# HB-UNI-SenAct-4-4-RC_V2_2.net
KiCad netlist of a schematic drawn in EAGLE
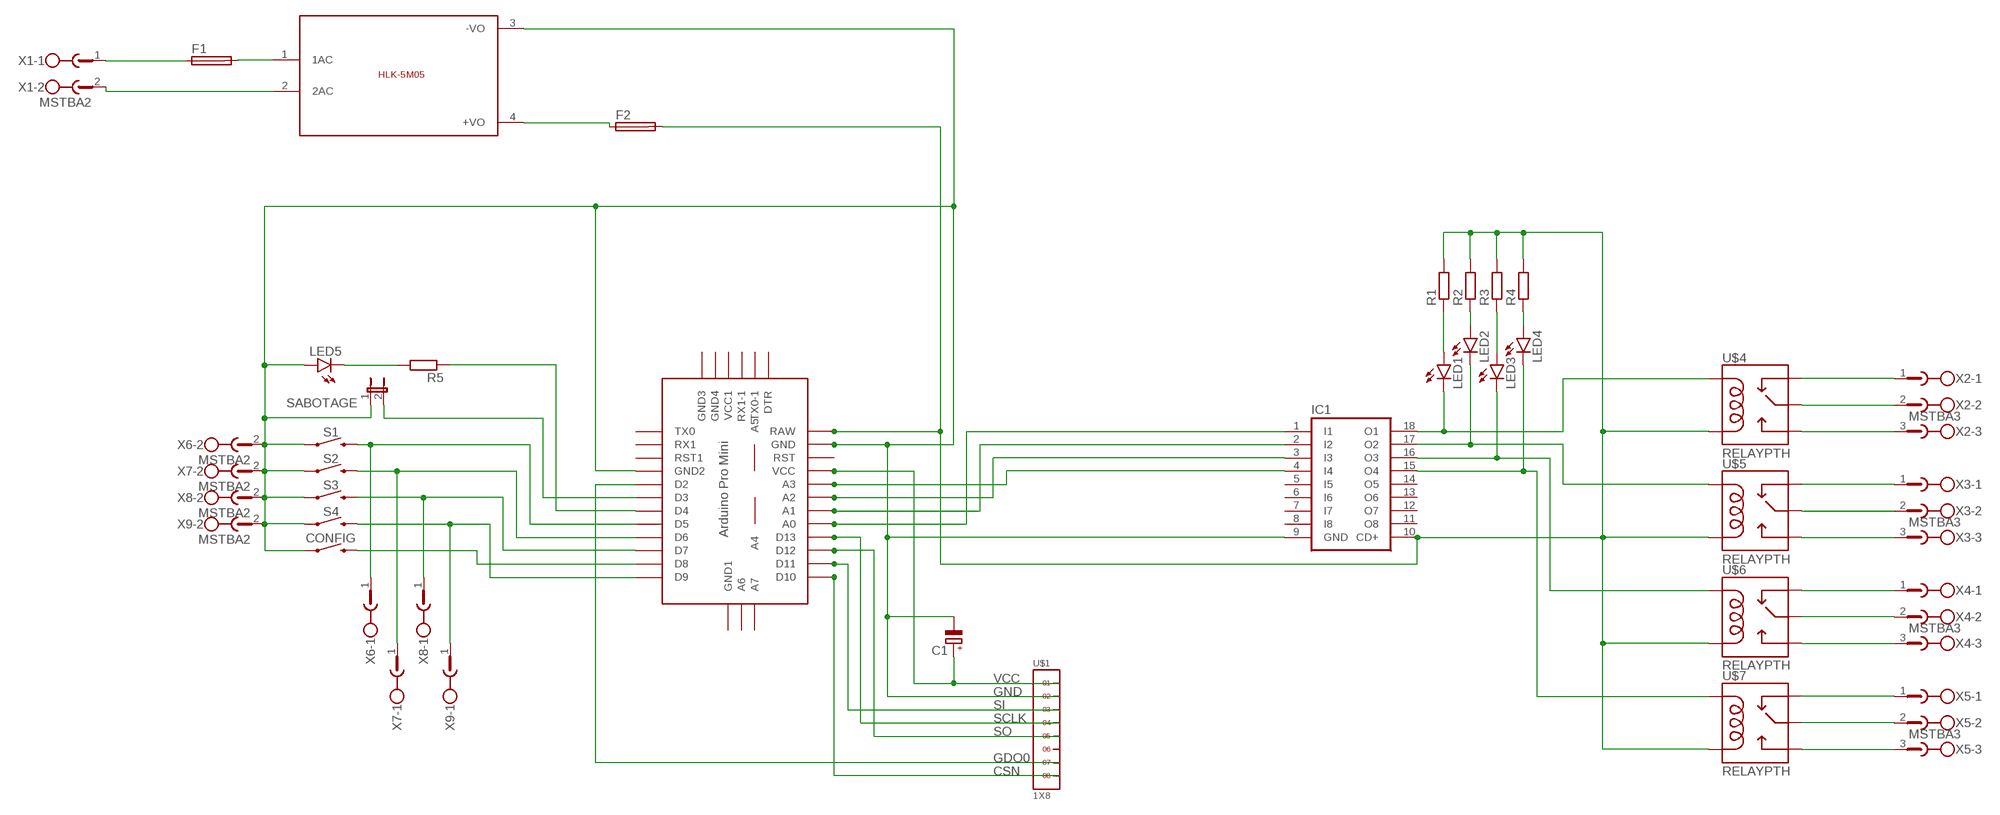
[diagram p0: schematic, sheet 1]

(export (version "E")
  (design (tool "Eeschema 10.0.6"))
  (components
    (comp (ref "C1")
      (value "CPOL-EUE2.5-5")
      (footprint "eagle-import:E2,5-5")
      (libsource (lib "eagle-import") (part "CPOL-EUE2.5-5"))
    )
    (comp (ref "CONFIG")
      (value "MOMENTARY-SWITCH-SPST-PTH-6.0MM-KIT")
      (footprint "eagle-import:TACTILE_SWITCH_PTH_6.0MM_KIT")
      (libsource (lib "eagle-import") (part "MOMENTARY-SWITCH-SPST-PTH-6.0MM-KIT"))
    )
    (comp (ref "F1")
      (value "SH22,5A")
      (footprint "eagle-import:SH22,5A")
      (fields (field (name "MPN") "0031.7701.11"))
      (libsource (lib "eagle-import") (part "SH22,5A"))
    )
    (comp (ref "F2")
      (value "SH22,5A")
      (footprint "eagle-import:SH22,5A")
      (fields (field (name "MPN") "0031.7701.11"))
      (libsource (lib "eagle-import") (part "SH22,5A"))
    )
    (comp (ref "IC1")
      (value "ULN2803A")
      (footprint "eagle-import:DIL18")
      (libsource (lib "eagle-import") (part "ULN2803A"))
    )
    (comp (ref "LED1")
      (value "LED3MM")
      (footprint "eagle-import:LED3MM")
      (libsource (lib "eagle-import") (part "LED3MM"))
    )
    (comp (ref "LED2")
      (value "LED3MM")
      (footprint "eagle-import:LED3MM")
      (libsource (lib "eagle-import") (part "LED3MM"))
    )
    (comp (ref "LED3")
      (value "LED3MM")
      (footprint "eagle-import:LED3MM")
      (libsource (lib "eagle-import") (part "LED3MM"))
    )
    (comp (ref "LED4")
      (value "LED3MM")
      (footprint "eagle-import:LED3MM")
      (libsource (lib "eagle-import") (part "LED3MM"))
    )
    (comp (ref "LED5")
      (value "LED3MM")
      (footprint "eagle-import:LED3MM")
      (libsource (lib "eagle-import") (part "LED3MM"))
    )
    (comp (ref "R1")
      (value "R-EU_0309/10")
      (footprint "eagle-import:0309_10")
      (libsource (lib "eagle-import") (part "R-EU_0309/10"))
    )
    (comp (ref "R2")
      (value "R-EU_0309/10")
      (footprint "eagle-import:0309_10")
      (libsource (lib "eagle-import") (part "R-EU_0309/10"))
    )
    (comp (ref "R3")
      (value "R-EU_0309/10")
      (footprint "eagle-import:0309_10")
      (libsource (lib "eagle-import") (part "R-EU_0309/10"))
    )
    (comp (ref "R4")
      (value "R-EU_0309/10")
      (footprint "eagle-import:0309_10")
      (libsource (lib "eagle-import") (part "R-EU_0309/10"))
    )
    (comp (ref "R5")
      (value "R-EU_0309/10")
      (footprint "eagle-import:0309_10")
      (libsource (lib "eagle-import") (part "R-EU_0309/10"))
    )
    (comp (ref "S1")
      (value "MOMENTARY-SWITCH-SPST-PTH-6.0MM")
      (footprint "eagle-import:TACTILE_SWITCH_PTH_6.0MM")
      (libsource (lib "eagle-import") (part "MOMENTARY-SWITCH-SPST-PTH-6.0MM"))
    )
    (comp (ref "S2")
      (value "MOMENTARY-SWITCH-SPST-PTH-6.0MM-KIT")
      (footprint "eagle-import:TACTILE_SWITCH_PTH_6.0MM_KIT")
      (libsource (lib "eagle-import") (part "MOMENTARY-SWITCH-SPST-PTH-6.0MM-KIT"))
    )
    (comp (ref "S3")
      (value "MOMENTARY-SWITCH-SPST-PTH-6.0MM-KIT")
      (footprint "eagle-import:TACTILE_SWITCH_PTH_6.0MM_KIT")
      (libsource (lib "eagle-import") (part "MOMENTARY-SWITCH-SPST-PTH-6.0MM-KIT"))
    )
    (comp (ref "S4")
      (value "MOMENTARY-SWITCH-SPST-PTH-6.0MM-KIT")
      (footprint "eagle-import:TACTILE_SWITCH_PTH_6.0MM_KIT")
      (libsource (lib "eagle-import") (part "MOMENTARY-SWITCH-SPST-PTH-6.0MM-KIT"))
    )
    (comp (ref "SABOTAGE")
      (value "JP1E")
      (footprint "eagle-import:JP1")
      (libsource (lib "eagle-import") (part "JP1E"))
    )
    (comp (ref "U$1")
      (value "1X8")
      (footprint "eagle-import:1X8")
      (libsource (lib "eagle-import") (part "1X8"))
    )
    (comp (ref "U$2")
      (value "ABK-PRO-MINI")
      (footprint "eagle-import:ABK-PRO-MINI")
      (libsource (lib "eagle-import") (part "ABK-PRO-MINI"))
    )
    (comp (ref "U$3")
      (value "5VDC/5W")
      (footprint "eagle-import:HLK-5M05")
      (libsource (lib "eagle-import") (part "HLK-5M05"))
    )
    (comp (ref "U$4")
      (value "RELAYPTH")
      (footprint "eagle-import:SRD-05VDC-SL-C")
      (libsource (lib "eagle-import") (part "RELAYPTH"))
    )
    (comp (ref "U$5")
      (value "RELAYPTH")
      (footprint "eagle-import:SRD-05VDC-SL-C")
      (libsource (lib "eagle-import") (part "RELAYPTH"))
    )
    (comp (ref "U$6")
      (value "RELAYPTH")
      (footprint "eagle-import:SRD-05VDC-SL-C")
      (libsource (lib "eagle-import") (part "RELAYPTH"))
    )
    (comp (ref "U$7")
      (value "RELAYPTH")
      (footprint "eagle-import:SRD-05VDC-SL-C")
      (libsource (lib "eagle-import") (part "RELAYPTH"))
    )
    (comp (ref "X1")
      (value "MSTBA2")
      (footprint "eagle-import:MSTBA2")
      (fields (field (name "MF") "FARNELL") (field (name "MPN") "1757242"))
      (libsource (lib "eagle-import") (part "MSTBA2"))
    )
    (comp (ref "X2")
      (value "MSTBA3")
      (footprint "eagle-import:MSTBA3")
      (fields (field (name "MF") "FARNELL") (field (name "MPN") "1757255"))
      (libsource (lib "eagle-import") (part "MSTBA3"))
    )
    (comp (ref "X3")
      (value "MSTBA3")
      (footprint "eagle-import:MSTBA3")
      (fields (field (name "MF") "FARNELL") (field (name "MPN") "1757255"))
      (libsource (lib "eagle-import") (part "MSTBA3"))
    )
    (comp (ref "X4")
      (value "MSTBA3")
      (footprint "eagle-import:MSTBA3")
      (fields (field (name "MF") "FARNELL") (field (name "MPN") "1757255"))
      (libsource (lib "eagle-import") (part "MSTBA3"))
    )
    (comp (ref "X5")
      (value "MSTBA3")
      (footprint "eagle-import:MSTBA3")
      (fields (field (name "MF") "FARNELL") (field (name "MPN") "1757255"))
      (libsource (lib "eagle-import") (part "MSTBA3"))
    )
    (comp (ref "X6")
      (value "MSTBA2")
      (footprint "eagle-import:MSTBA2")
      (fields (field (name "MF") "FARNELL") (field (name "MPN") "1757242"))
      (libsource (lib "eagle-import") (part "MSTBA2"))
    )
    (comp (ref "X7")
      (value "MSTBA2")
      (footprint "eagle-import:MSTBA2")
      (fields (field (name "MF") "FARNELL") (field (name "MPN") "1757242"))
      (libsource (lib "eagle-import") (part "MSTBA2"))
    )
    (comp (ref "X8")
      (value "MSTBA2")
      (footprint "eagle-import:MSTBA2")
      (fields (field (name "MF") "FARNELL") (field (name "MPN") "1757242"))
      (libsource (lib "eagle-import") (part "MSTBA2"))
    )
    (comp (ref "X9")
      (value "MSTBA2")
      (footprint "eagle-import:MSTBA2")
      (fields (field (name "MF") "FARNELL") (field (name "MPN") "1757242"))
      (libsource (lib "eagle-import") (part "MSTBA2"))
    )
  )
  (nets
    (net (code "1") (name "/CSN") (class "Default")
      (node (ref "U$1") (pin "8") (pinfunction "8_8") (pintype "bidirectional"))
      (node (ref "U$2") (pin "D10") (pinfunction "D10_D10") (pintype "bidirectional"))
    )
    (net (code "2") (name "/GDO0") (class "Default")
      (node (ref "U$1") (pin "7") (pinfunction "7_7") (pintype "bidirectional"))
      (node (ref "U$2") (pin "D2") (pinfunction "D2_D2") (pintype "bidirectional"))
    )
    (net (code "3") (name "/GND") (class "Default")
      (node (ref "C1") (pin "-") (pinfunction "-_-") (pintype "passive"))
      (node (ref "CONFIG") (pin "1") (pinfunction "1_1") (pintype "passive"))
      (node (ref "IC1") (pin "9") (pinfunction "GND_9") (pintype "power_in"))
      (node (ref "LED5") (pin "A") (pinfunction "A_A") (pintype "passive"))
      (node (ref "S1") (pin "1") (pinfunction "1_1") (pintype "passive"))
      (node (ref "S2") (pin "1") (pinfunction "1_1") (pintype "passive"))
      (node (ref "S3") (pin "1") (pinfunction "1_1") (pintype "passive"))
      (node (ref "S4") (pin "1") (pinfunction "1_1") (pintype "passive"))
      (node (ref "SABOTAGE") (pin "1") (pinfunction "1_1") (pintype "passive"))
      (node (ref "U$1") (pin "2") (pinfunction "2_2") (pintype "bidirectional"))
      (node (ref "U$2") (pin "GND") (pinfunction "GND_GND") (pintype "bidirectional"))
      (node (ref "U$2") (pin "GND1") (pinfunction "GND2_GND1") (pintype "bidirectional"))
      (node (ref "U$3") (pin "3") (pinfunction "-VO_3") (pintype "bidirectional"))
      (node (ref "X6") (pin "2") (pinfunction "1_2") (pintype "passive"))
      (node (ref "X7") (pin "2") (pinfunction "1_2") (pintype "passive"))
      (node (ref "X8") (pin "2") (pinfunction "1_2") (pintype "passive"))
      (node (ref "X9") (pin "2") (pinfunction "1_2") (pintype "passive"))
    )
    (net (code "4") (name "/SCLK") (class "Default")
      (node (ref "U$1") (pin "4") (pinfunction "4_4") (pintype "bidirectional"))
      (node (ref "U$2") (pin "D13") (pinfunction "D13_D13") (pintype "bidirectional"))
    )
    (net (code "5") (name "/SI") (class "Default")
      (node (ref "U$1") (pin "3") (pinfunction "3_3") (pintype "bidirectional"))
      (node (ref "U$2") (pin "D11") (pinfunction "D11_D11") (pintype "bidirectional"))
    )
    (net (code "6") (name "/SO") (class "Default")
      (node (ref "U$1") (pin "5") (pinfunction "5_5") (pintype "bidirectional"))
      (node (ref "U$2") (pin "D12") (pinfunction "D12_D12") (pintype "bidirectional"))
    )
    (net (code "7") (name "/VCC") (class "Default")
      (node (ref "C1") (pin "+") (pinfunction "+_+") (pintype "passive"))
      (node (ref "U$1") (pin "1") (pinfunction "1_1") (pintype "bidirectional"))
      (node (ref "U$2") (pin "VCC") (pinfunction "VCC_VCC") (pintype "bidirectional"))
    )
    (net (code "8") (name "Net-(CONFIG-2)") (class "Default")
      (node (ref "CONFIG") (pin "3") (pinfunction "2_3") (pintype "passive"))
      (node (ref "U$2") (pin "D8") (pinfunction "D8_D8") (pintype "bidirectional"))
    )
    (net (code "9") (name "Net-(F1-Pad1)") (class "Default")
      (node (ref "F1") (pin "1") (pinfunction "1_1") (pintype "passive"))
      (node (ref "X1") (pin "1") (pinfunction "1_1") (pintype "passive"))
    )
    (net (code "10") (name "Net-(IC1-CD+)") (class "Default")
      (node (ref "F2") (pin "2") (pinfunction "2_2") (pintype "passive"))
      (node (ref "IC1") (pin "10") (pinfunction "CD+_10") (pintype "passive"))
      (node (ref "R1") (pin "2") (pinfunction "2_2") (pintype "passive"))
      (node (ref "R2") (pin "2") (pinfunction "2_2") (pintype "passive"))
      (node (ref "R3") (pin "2") (pinfunction "2_2") (pintype "passive"))
      (node (ref "R4") (pin "2") (pinfunction "2_2") (pintype "passive"))
      (node (ref "U$2") (pin "RAW") (pinfunction "RAW_RAW") (pintype "bidirectional"))
      (node (ref "U$4") (pin "COIL0") (pinfunction "COIL0_COIL0") (pintype "bidirectional"))
      (node (ref "U$5") (pin "COIL0") (pinfunction "COIL0_COIL0") (pintype "bidirectional"))
      (node (ref "U$6") (pin "COIL0") (pinfunction "COIL0_COIL0") (pintype "bidirectional"))
      (node (ref "U$7") (pin "COIL0") (pinfunction "COIL0_COIL0") (pintype "bidirectional"))
    )
    (net (code "11") (name "Net-(IC1-I1)") (class "Default")
      (node (ref "IC1") (pin "1") (pinfunction "I1_1") (pintype "input"))
      (node (ref "U$2") (pin "A0") (pinfunction "A0_A0") (pintype "bidirectional"))
    )
    (net (code "12") (name "Net-(IC1-I2)") (class "Default")
      (node (ref "IC1") (pin "2") (pinfunction "I2_2") (pintype "input"))
      (node (ref "U$2") (pin "A1") (pinfunction "A1_A1") (pintype "bidirectional"))
    )
    (net (code "13") (name "Net-(IC1-I3)") (class "Default")
      (node (ref "IC1") (pin "3") (pinfunction "I3_3") (pintype "input"))
      (node (ref "U$2") (pin "A2") (pinfunction "A2_A2") (pintype "bidirectional"))
    )
    (net (code "14") (name "Net-(IC1-I4)") (class "Default")
      (node (ref "IC1") (pin "4") (pinfunction "I4_4") (pintype "input"))
      (node (ref "U$2") (pin "A3") (pinfunction "A3_A3") (pintype "bidirectional"))
    )
    (net (code "15") (name "Net-(IC1-O1)") (class "Default")
      (node (ref "IC1") (pin "18") (pinfunction "O1_18") (pintype "open_collector"))
      (node (ref "LED1") (pin "K") (pinfunction "C_K") (pintype "passive"))
      (node (ref "U$4") (pin "COIL1") (pinfunction "COIL1_COIL1") (pintype "bidirectional"))
    )
    (net (code "16") (name "Net-(IC1-O2)") (class "Default")
      (node (ref "IC1") (pin "17") (pinfunction "O2_17") (pintype "open_collector"))
      (node (ref "LED2") (pin "K") (pinfunction "C_K") (pintype "passive"))
      (node (ref "U$5") (pin "COIL1") (pinfunction "COIL1_COIL1") (pintype "bidirectional"))
    )
    (net (code "17") (name "Net-(IC1-O3)") (class "Default")
      (node (ref "IC1") (pin "16") (pinfunction "O3_16") (pintype "open_collector"))
      (node (ref "LED3") (pin "K") (pinfunction "C_K") (pintype "passive"))
      (node (ref "U$6") (pin "COIL1") (pinfunction "COIL1_COIL1") (pintype "bidirectional"))
    )
    (net (code "18") (name "Net-(IC1-O4)") (class "Default")
      (node (ref "IC1") (pin "15") (pinfunction "O4_15") (pintype "open_collector"))
      (node (ref "LED4") (pin "K") (pinfunction "C_K") (pintype "passive"))
      (node (ref "U$7") (pin "COIL1") (pinfunction "COIL1_COIL1") (pintype "bidirectional"))
    )
    (net (code "19") (name "Net-(LED1-PadA)") (class "Default")
      (node (ref "LED1") (pin "A") (pinfunction "A_A") (pintype "passive"))
      (node (ref "R1") (pin "1") (pinfunction "1_1") (pintype "passive"))
    )
    (net (code "20") (name "Net-(LED2-PadA)") (class "Default")
      (node (ref "LED2") (pin "A") (pinfunction "A_A") (pintype "passive"))
      (node (ref "R2") (pin "1") (pinfunction "1_1") (pintype "passive"))
    )
    (net (code "21") (name "Net-(LED3-PadA)") (class "Default")
      (node (ref "LED3") (pin "A") (pinfunction "A_A") (pintype "passive"))
      (node (ref "R3") (pin "1") (pinfunction "1_1") (pintype "passive"))
    )
    (net (code "22") (name "Net-(LED4-PadA)") (class "Default")
      (node (ref "LED4") (pin "A") (pinfunction "A_A") (pintype "passive"))
      (node (ref "R4") (pin "1") (pinfunction "1_1") (pintype "passive"))
    )
    (net (code "23") (name "Net-(LED5-C)") (class "Default")
      (node (ref "LED5") (pin "K") (pinfunction "C_K") (pintype "passive"))
      (node (ref "R5") (pin "2") (pinfunction "2_2") (pintype "passive"))
    )
    (net (code "24") (name "Net-(R5-Pad1)") (class "Default")
      (node (ref "R5") (pin "1") (pinfunction "1_1") (pintype "passive"))
      (node (ref "U$2") (pin "D4") (pinfunction "D4_D4") (pintype "bidirectional"))
    )
    (net (code "25") (name "Net-(S1-2)") (class "Default")
      (node (ref "S1") (pin "3") (pinfunction "2_3") (pintype "passive"))
      (node (ref "U$2") (pin "D5") (pinfunction "D5_D5") (pintype "bidirectional"))
      (node (ref "X6") (pin "1") (pinfunction "1_1") (pintype "passive"))
    )
    (net (code "26") (name "Net-(S2-2)") (class "Default")
      (node (ref "S2") (pin "3") (pinfunction "2_3") (pintype "passive"))
      (node (ref "U$2") (pin "D6") (pinfunction "D6_D6") (pintype "bidirectional"))
      (node (ref "X7") (pin "1") (pinfunction "1_1") (pintype "passive"))
    )
    (net (code "27") (name "Net-(S3-2)") (class "Default")
      (node (ref "S3") (pin "3") (pinfunction "2_3") (pintype "passive"))
      (node (ref "U$2") (pin "D7") (pinfunction "D7_D7") (pintype "bidirectional"))
      (node (ref "X8") (pin "1") (pinfunction "1_1") (pintype "passive"))
    )
    (net (code "28") (name "Net-(S4-2)") (class "Default")
      (node (ref "S4") (pin "3") (pinfunction "2_3") (pintype "passive"))
      (node (ref "U$2") (pin "D9") (pinfunction "D9_D9") (pintype "bidirectional"))
      (node (ref "X9") (pin "1") (pinfunction "1_1") (pintype "passive"))
    )
    (net (code "29") (name "Net-(SABOTAGE-Pad2)") (class "Default")
      (node (ref "SABOTAGE") (pin "2") (pinfunction "2_2") (pintype "passive"))
      (node (ref "U$2") (pin "D3") (pinfunction "D3_D3") (pintype "bidirectional"))
    )
    (net (code "30") (name "Net-(U$3-+VO)") (class "Default")
      (node (ref "F2") (pin "1") (pinfunction "1_1") (pintype "passive"))
      (node (ref "U$3") (pin "4") (pinfunction "+VO_4") (pintype "bidirectional"))
    )
    (net (code "31") (name "Net-(U$3-1AC)") (class "Default")
      (node (ref "F1") (pin "2") (pinfunction "2_2") (pintype "passive"))
      (node (ref "U$3") (pin "1") (pinfunction "1AC_1") (pintype "bidirectional"))
    )
    (net (code "32") (name "Net-(U$3-2AC)") (class "Default")
      (node (ref "U$3") (pin "2") (pinfunction "2AC_2") (pintype "bidirectional"))
      (node (ref "X1") (pin "2") (pinfunction "1_2") (pintype "passive"))
    )
    (net (code "33") (name "Net-(U$4-SWCLOSE)") (class "Default")
      (node (ref "U$4") (pin "SWCLOSED") (pinfunction "SWCLOSE_SWCLOSED") (pintype "bidirectional"))
      (node (ref "X2") (pin "1") (pinfunction "1_1") (pintype "passive"))
    )
    (net (code "34") (name "Net-(U$5-SWCLOSE)") (class "Default")
      (node (ref "U$5") (pin "SWCLOSED") (pinfunction "SWCLOSE_SWCLOSED") (pintype "bidirectional"))
      (node (ref "X3") (pin "1") (pinfunction "1_1") (pintype "passive"))
    )
    (net (code "35") (name "Net-(U$6-SWCLOSE)") (class "Default")
      (node (ref "U$6") (pin "SWCLOSED") (pinfunction "SWCLOSE_SWCLOSED") (pintype "bidirectional"))
      (node (ref "X4") (pin "1") (pinfunction "1_1") (pintype "passive"))
    )
    (net (code "36") (name "Net-(U$7-SWCLOSE)") (class "Default")
      (node (ref "U$7") (pin "SWCLOSED") (pinfunction "SWCLOSE_SWCLOSED") (pintype "bidirectional"))
      (node (ref "X5") (pin "1") (pinfunction "1_1") (pintype "passive"))
    )
    (net (code "37") (name "Net-(X2B-1)") (class "Default")
      (node (ref "U$4") (pin "SWCOMMON") (pinfunction "SWCOMMON_SWCOMMON") (pintype "bidirectional"))
      (node (ref "X2") (pin "2") (pinfunction "1_2") (pintype "passive"))
    )
    (net (code "38") (name "Net-(X2C-1)") (class "Default")
      (node (ref "U$4") (pin "SWOPEN") (pinfunction "SWOPEN_SWOPEN") (pintype "bidirectional"))
      (node (ref "X2") (pin "3") (pinfunction "1_3") (pintype "passive"))
    )
    (net (code "39") (name "Net-(X3B-1)") (class "Default")
      (node (ref "U$5") (pin "SWCOMMON") (pinfunction "SWCOMMON_SWCOMMON") (pintype "bidirectional"))
      (node (ref "X3") (pin "2") (pinfunction "1_2") (pintype "passive"))
    )
    (net (code "40") (name "Net-(X3C-1)") (class "Default")
      (node (ref "U$5") (pin "SWOPEN") (pinfunction "SWOPEN_SWOPEN") (pintype "bidirectional"))
      (node (ref "X3") (pin "3") (pinfunction "1_3") (pintype "passive"))
    )
    (net (code "41") (name "Net-(X4B-1)") (class "Default")
      (node (ref "U$6") (pin "SWCOMMON") (pinfunction "SWCOMMON_SWCOMMON") (pintype "bidirectional"))
      (node (ref "X4") (pin "2") (pinfunction "1_2") (pintype "passive"))
    )
    (net (code "42") (name "Net-(X4C-1)") (class "Default")
      (node (ref "U$6") (pin "SWOPEN") (pinfunction "SWOPEN_SWOPEN") (pintype "bidirectional"))
      (node (ref "X4") (pin "3") (pinfunction "1_3") (pintype "passive"))
    )
    (net (code "43") (name "Net-(X5B-1)") (class "Default")
      (node (ref "U$7") (pin "SWCOMMON") (pinfunction "SWCOMMON_SWCOMMON") (pintype "bidirectional"))
      (node (ref "X5") (pin "2") (pinfunction "1_2") (pintype "passive"))
    )
    (net (code "44") (name "Net-(X5C-1)") (class "Default")
      (node (ref "U$7") (pin "SWOPEN") (pinfunction "SWOPEN_SWOPEN") (pintype "bidirectional"))
      (node (ref "X5") (pin "3") (pinfunction "1_3") (pintype "passive"))
    )
    (net (code "45") (name "unconnected-(IC1-I5-Pad5)") (class "Default")
      (node (ref "IC1") (pin "5") (pinfunction "I5_5") (pintype "input"))
    )
    (net (code "46") (name "unconnected-(IC1-I6-Pad6)") (class "Default")
      (node (ref "IC1") (pin "6") (pinfunction "I6_6") (pintype "input"))
    )
    (net (code "47") (name "unconnected-(IC1-I7-Pad7)") (class "Default")
      (node (ref "IC1") (pin "7") (pinfunction "I7_7") (pintype "input"))
    )
    (net (code "48") (name "unconnected-(IC1-I8-Pad8)") (class "Default")
      (node (ref "IC1") (pin "8") (pinfunction "I8_8") (pintype "input"))
    )
    (net (code "49") (name "unconnected-(IC1-O5-Pad14)") (class "Default")
      (node (ref "IC1") (pin "14") (pinfunction "O5_14") (pintype "open_collector"))
    )
    (net (code "50") (name "unconnected-(IC1-O6-Pad13)") (class "Default")
      (node (ref "IC1") (pin "13") (pinfunction "O6_13") (pintype "open_collector"))
    )
    (net (code "51") (name "unconnected-(IC1-O7-Pad12)") (class "Default")
      (node (ref "IC1") (pin "12") (pinfunction "O7_12") (pintype "open_collector"))
    )
    (net (code "52") (name "unconnected-(IC1-O8-Pad11)") (class "Default")
      (node (ref "IC1") (pin "11") (pinfunction "O8_11") (pintype "open_collector"))
    )
    (net (code "53") (name "unconnected-(U$1-Pad6)") (class "Default")
      (node (ref "U$1") (pin "6") (pinfunction "6_6") (pintype "bidirectional"))
    )
    (net (code "54") (name "unconnected-(U$2-GND1-PadGND4)") (class "Default")
      (node (ref "U$2") (pin "GND4") (pinfunction "GND1_GND4") (pintype "bidirectional"))
    )
    (net (code "55") (name "unconnected-(U$2-GND3-PadGND2)") (class "Default")
      (node (ref "U$2") (pin "GND2") (pinfunction "GND3_GND2") (pintype "bidirectional"))
    )
    (net (code "56") (name "unconnected-(U$2-GND4-PadGND3)") (class "Default")
      (node (ref "U$2") (pin "GND3") (pinfunction "GND4_GND3") (pintype "bidirectional"))
    )
    (net (code "57") (name "unconnected-(U$2-PadA4)") (class "Default")
      (node (ref "U$2") (pin "A4") (pinfunction "A4_A4") (pintype "bidirectional"))
    )
    (net (code "58") (name "unconnected-(U$2-PadA5)") (class "Default")
      (node (ref "U$2") (pin "A5") (pinfunction "A5_A5") (pintype "bidirectional"))
    )
    (net (code "59") (name "unconnected-(U$2-PadA6)") (class "Default")
      (node (ref "U$2") (pin "A6") (pinfunction "A6_A6") (pintype "bidirectional"))
    )
    (net (code "60") (name "unconnected-(U$2-PadA7)") (class "Default")
      (node (ref "U$2") (pin "A7") (pinfunction "A7_A7") (pintype "bidirectional"))
    )
    (net (code "61") (name "unconnected-(U$2-PadDTR)") (class "Default")
      (node (ref "U$2") (pin "DTR") (pinfunction "DTR_DTR") (pintype "bidirectional"))
    )
    (net (code "62") (name "unconnected-(U$2-PadRST)") (class "Default")
      (node (ref "U$2") (pin "RST") (pinfunction "RST_RST") (pintype "bidirectional"))
    )
    (net (code "63") (name "unconnected-(U$2-PadRST1)") (class "Default")
      (node (ref "U$2") (pin "RST1") (pinfunction "RST1_RST1") (pintype "bidirectional"))
    )
    (net (code "64") (name "unconnected-(U$2-PadRX1)") (class "Default")
      (node (ref "U$2") (pin "RX1") (pinfunction "RX1_RX1") (pintype "bidirectional"))
    )
    (net (code "65") (name "unconnected-(U$2-PadRX1-1)") (class "Default")
      (node (ref "U$2") (pin "RX1-1") (pinfunction "RX1-1_RX1-1") (pintype "bidirectional"))
    )
    (net (code "66") (name "unconnected-(U$2-PadTX0)") (class "Default")
      (node (ref "U$2") (pin "TX0") (pinfunction "TX0_TX0") (pintype "bidirectional"))
    )
    (net (code "67") (name "unconnected-(U$2-PadTX0-1)") (class "Default")
      (node (ref "U$2") (pin "TX0-1") (pinfunction "TX0-1_TX0-1") (pintype "bidirectional"))
    )
    (net (code "68") (name "unconnected-(U$2-PadVCC1)") (class "Default")
      (node (ref "U$2") (pin "VCC1") (pinfunction "VCC1_VCC1") (pintype "bidirectional"))
    )
  )
)
